# Oblig4.net
KiCad netlist of a schematic drawn in EAGLE
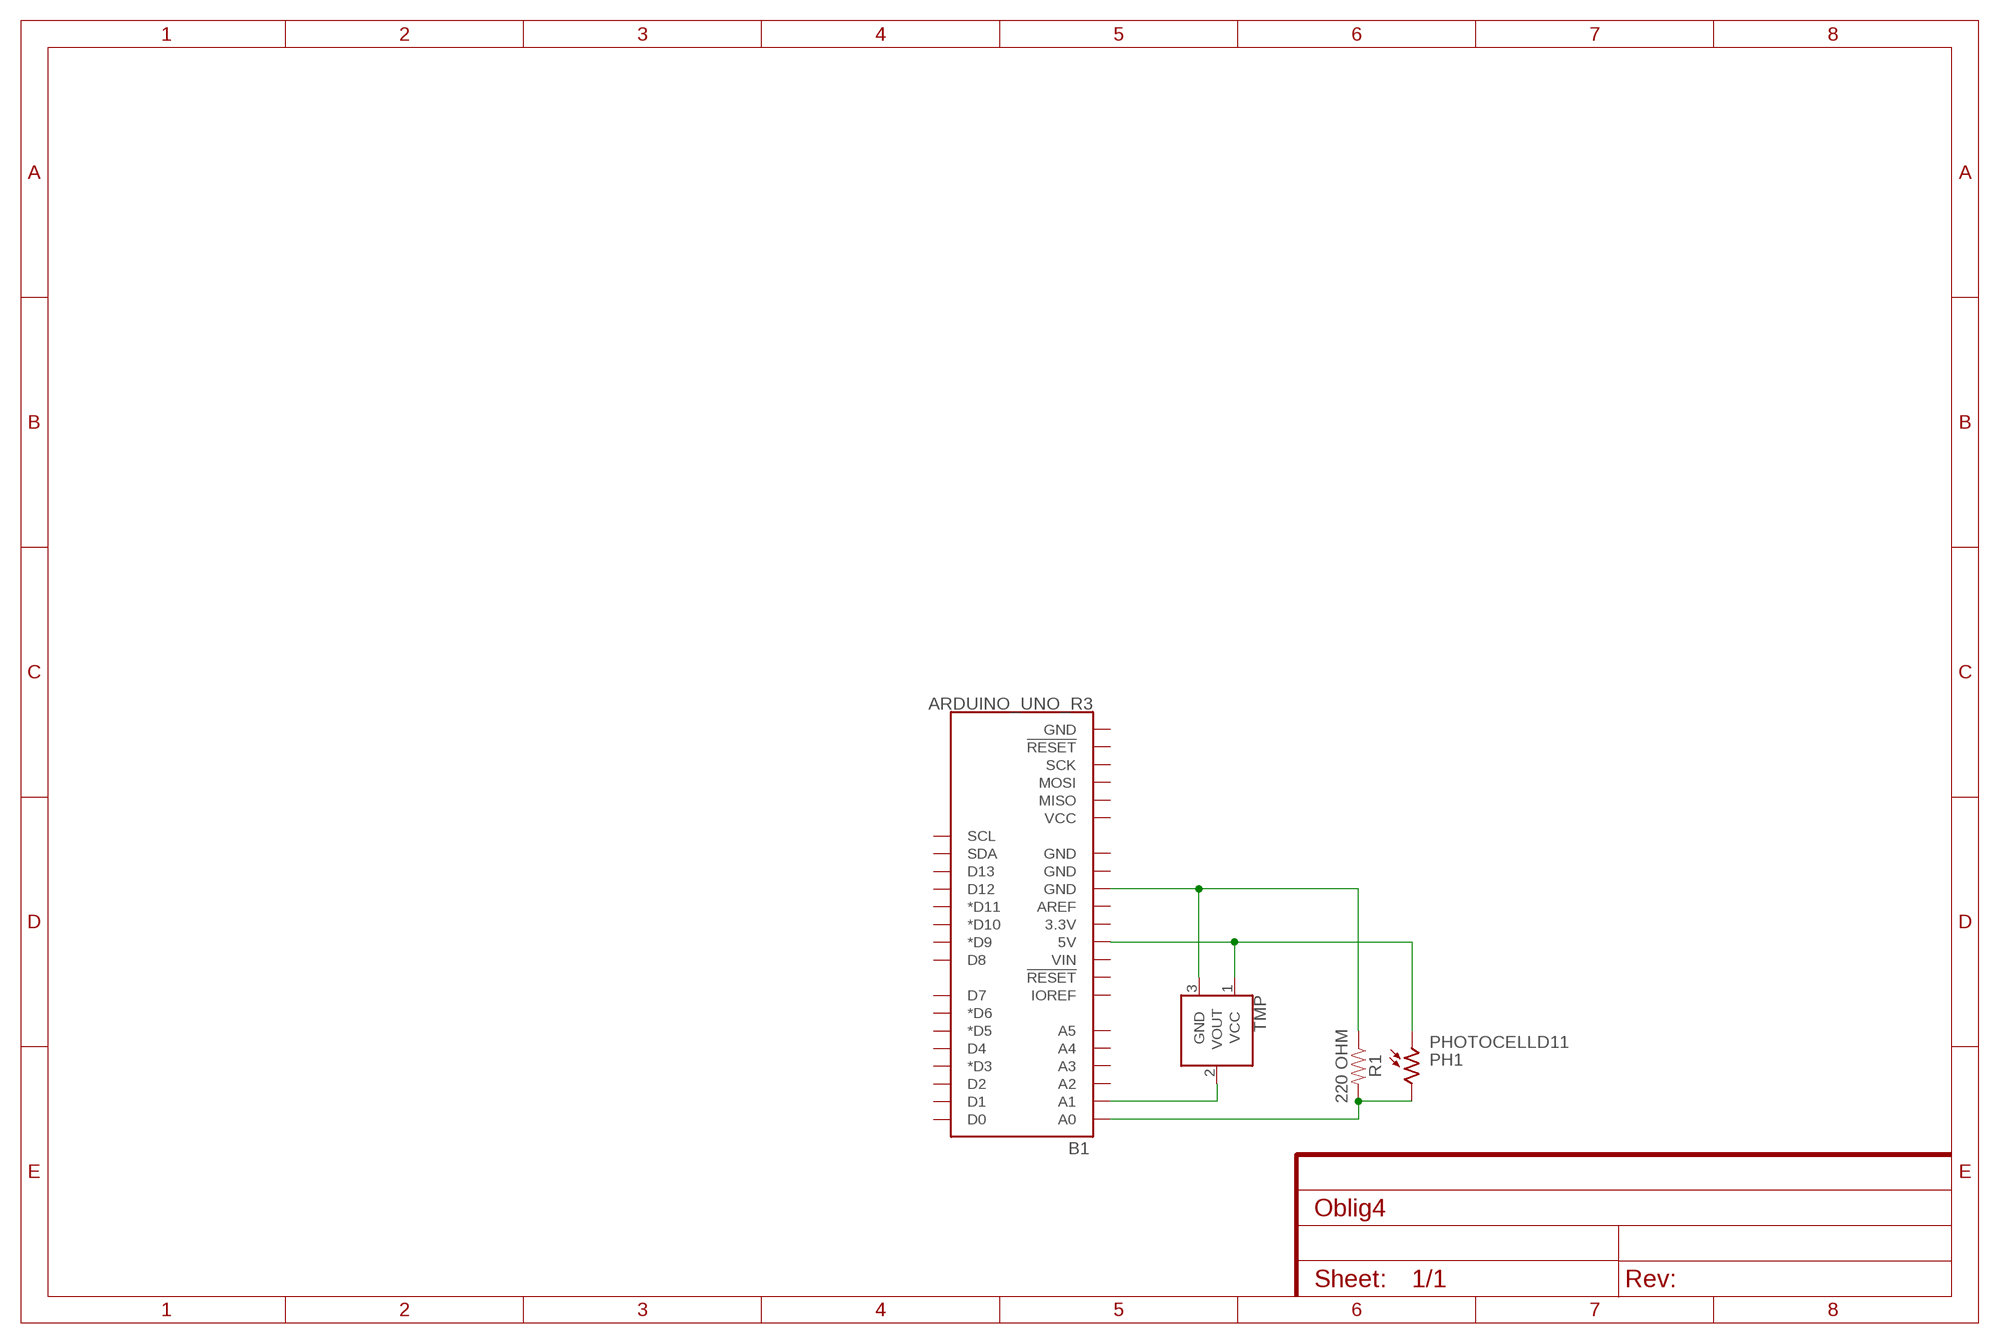
[diagram p0: schematic, sheet 1]

(export (version "E")
  (design (tool "Eeschema 10.0.6"))
  (components
    (comp (ref "B1")
      (value "ARDUINO_UNO_R3")
      (footprint "eagle-import:ARDUINO_R3")
      (libsource (lib "eagle-import") (part "ARDUINO_UNO_R3"))
    )
    (comp (ref "PH1")
      (value "PHOTOCELLD11")
      (footprint "eagle-import:D11XX_H")
      (libsource (lib "eagle-import") (part "PHOTOCELLD11"))
    )
    (comp (ref "R1")
      (value "220 OHM")
      (footprint "eagle-import:AXIAL-0.3")
      (fields (field (name "PROD_ID") "220 OHM"))
      (libsource (lib "eagle-import") (part "RESISTORAXIAL-0.3"))
    )
    (comp (ref "TMP")
      (value "TMP36GT9")
      (footprint "eagle-import:TO-92")
      (libsource (lib "eagle-import") (part "TMP36GT9"))
    )
  )
  (nets
    (net (code "1") (name "Net-(R1-1)") (class "Default")
      (node (ref "B1") (pin "GND@4") (pinfunction "GND_GND@4") (pintype "bidirectional"))
      (node (ref "R1") (pin "P$1") (pinfunction "1_P$1") (pintype "passive"))
      (node (ref "TMP") (pin "3") (pinfunction "GND_3") (pintype "bidirectional"))
    )
    (net (code "2") (name "Net-(R1-2)") (class "Default")
      (node (ref "B1") (pin "A0") (pinfunction "A0_A0") (pintype "bidirectional"))
      (node (ref "PH1") (pin "2") (pinfunction "2_2") (pintype "passive"))
      (node (ref "R1") (pin "P$2") (pinfunction "2_P$2") (pintype "passive"))
    )
    (net (code "3") (name "Net-(TMP-VCC)") (class "Default")
      (node (ref "B1") (pin "5V") (pinfunction "5V_5V") (pintype "bidirectional"))
      (node (ref "PH1") (pin "1") (pinfunction "1_1") (pintype "passive"))
      (node (ref "TMP") (pin "1") (pinfunction "VCC_1") (pintype "bidirectional"))
    )
    (net (code "4") (name "Net-(TMP-VOUT)") (class "Default")
      (node (ref "B1") (pin "A1") (pinfunction "A1_A1") (pintype "bidirectional"))
      (node (ref "TMP") (pin "2") (pinfunction "VOUT_2") (pintype "bidirectional"))
    )
    (net (code "5") (name "unconnected-(B1-*D3-PadD3)") (class "Default")
      (node (ref "B1") (pin "D3") (pinfunction "*D3_D3") (pintype "bidirectional"))
    )
    (net (code "6") (name "unconnected-(B1-*D5-PadD5)") (class "Default")
      (node (ref "B1") (pin "D5") (pinfunction "*D5_D5") (pintype "bidirectional"))
    )
    (net (code "7") (name "unconnected-(B1-*D6-PadD6)") (class "Default")
      (node (ref "B1") (pin "D6") (pinfunction "*D6_D6") (pintype "bidirectional"))
    )
    (net (code "8") (name "unconnected-(B1-*D9-PadD9)") (class "Default")
      (node (ref "B1") (pin "D9") (pinfunction "*D9_D9") (pintype "bidirectional"))
    )
    (net (code "9") (name "unconnected-(B1-*D10-PadD10)") (class "Default")
      (node (ref "B1") (pin "D10") (pinfunction "*D10_D10") (pintype "bidirectional"))
    )
    (net (code "10") (name "unconnected-(B1-*D11-PadD11)") (class "Default")
      (node (ref "B1") (pin "D11") (pinfunction "*D11_D11") (pintype "bidirectional"))
    )
    (net (code "11") (name "unconnected-(B1-GND-PadGND@1)") (class "Default")
      (node (ref "B1") (pin "GND@1") (pinfunction "GND_GND@1") (pintype "bidirectional"))
    )
    (net (code "12") (name "unconnected-(B1-GND-PadGND@2)") (class "Default")
      (node (ref "B1") (pin "GND@2") (pinfunction "GND_GND@2") (pintype "bidirectional"))
    )
    (net (code "13") (name "unconnected-(B1-GND-PadGND@3)") (class "Default")
      (node (ref "B1") (pin "GND@3") (pinfunction "GND_GND@3") (pintype "bidirectional"))
    )
    (net (code "14") (name "unconnected-(B1-Pad3.3V)") (class "Default")
      (node (ref "B1") (pin "3.3V") (pinfunction "3.3V_3.3V") (pintype "bidirectional"))
    )
    (net (code "15") (name "unconnected-(B1-PadA2)") (class "Default")
      (node (ref "B1") (pin "A2") (pinfunction "A2_A2") (pintype "bidirectional"))
    )
    (net (code "16") (name "unconnected-(B1-PadA3)") (class "Default")
      (node (ref "B1") (pin "A3") (pinfunction "A3_A3") (pintype "bidirectional"))
    )
    (net (code "17") (name "unconnected-(B1-PadA4)") (class "Default")
      (node (ref "B1") (pin "A4") (pinfunction "A4_A4") (pintype "bidirectional"))
    )
    (net (code "18") (name "unconnected-(B1-PadA5)") (class "Default")
      (node (ref "B1") (pin "A5") (pinfunction "A5_A5") (pintype "bidirectional"))
    )
    (net (code "19") (name "unconnected-(B1-PadAREF)") (class "Default")
      (node (ref "B1") (pin "AREF") (pinfunction "AREF_AREF") (pintype "bidirectional"))
    )
    (net (code "20") (name "unconnected-(B1-PadD0)") (class "Default")
      (node (ref "B1") (pin "D0") (pinfunction "D0_D0") (pintype "bidirectional"))
    )
    (net (code "21") (name "unconnected-(B1-PadD1)") (class "Default")
      (node (ref "B1") (pin "D1") (pinfunction "D1_D1") (pintype "bidirectional"))
    )
    (net (code "22") (name "unconnected-(B1-PadD2)") (class "Default")
      (node (ref "B1") (pin "D2") (pinfunction "D2_D2") (pintype "bidirectional"))
    )
    (net (code "23") (name "unconnected-(B1-PadD4)") (class "Default")
      (node (ref "B1") (pin "D4") (pinfunction "D4_D4") (pintype "bidirectional"))
    )
    (net (code "24") (name "unconnected-(B1-PadD7)") (class "Default")
      (node (ref "B1") (pin "D7") (pinfunction "D7_D7") (pintype "bidirectional"))
    )
    (net (code "25") (name "unconnected-(B1-PadD8)") (class "Default")
      (node (ref "B1") (pin "D8") (pinfunction "D8_D8") (pintype "bidirectional"))
    )
    (net (code "26") (name "unconnected-(B1-PadD12)") (class "Default")
      (node (ref "B1") (pin "D12") (pinfunction "D12_D12") (pintype "bidirectional"))
    )
    (net (code "27") (name "unconnected-(B1-PadD13)") (class "Default")
      (node (ref "B1") (pin "D13") (pinfunction "D13_D13") (pintype "bidirectional"))
    )
    (net (code "28") (name "unconnected-(B1-PadIOREF)") (class "Default")
      (node (ref "B1") (pin "IOREF") (pinfunction "IOREF_IOREF") (pintype "bidirectional"))
    )
    (net (code "29") (name "unconnected-(B1-PadMISO)") (class "Default")
      (node (ref "B1") (pin "MISO") (pinfunction "MISO_MISO") (pintype "bidirectional"))
    )
    (net (code "30") (name "unconnected-(B1-PadMOSI)") (class "Default")
      (node (ref "B1") (pin "MOSI") (pinfunction "MOSI_MOSI") (pintype "bidirectional"))
    )
    (net (code "31") (name "unconnected-(B1-PadSCK)") (class "Default")
      (node (ref "B1") (pin "SCK") (pinfunction "SCK_SCK") (pintype "bidirectional"))
    )
    (net (code "32") (name "unconnected-(B1-PadSCL)") (class "Default")
      (node (ref "B1") (pin "SCL") (pinfunction "SCL_SCL") (pintype "bidirectional"))
    )
    (net (code "33") (name "unconnected-(B1-PadSDA)") (class "Default")
      (node (ref "B1") (pin "SDA") (pinfunction "SDA_SDA") (pintype "bidirectional"))
    )
    (net (code "34") (name "unconnected-(B1-PadVCC)") (class "Default")
      (node (ref "B1") (pin "VCC") (pinfunction "VCC_VCC") (pintype "bidirectional"))
    )
    (net (code "35") (name "unconnected-(B1-PadVIN)") (class "Default")
      (node (ref "B1") (pin "VIN") (pinfunction "VIN_VIN") (pintype "bidirectional"))
    )
    (net (code "36") (name "unconnected-(B1-~{RESET}-PadRESET@1)") (class "Default")
      (node (ref "B1") (pin "RESET@1") (pinfunction "~{RESET}_RESET@1") (pintype "bidirectional"))
    )
    (net (code "37") (name "unconnected-(B1-~{RESET}-PadRESET@2)") (class "Default")
      (node (ref "B1") (pin "RESET@2") (pinfunction "~{RESET}_RESET@2") (pintype "bidirectional"))
    )
  )
)
